# sa612_rcvr.net
KiCad netlist of a schematic drawn in EAGLE
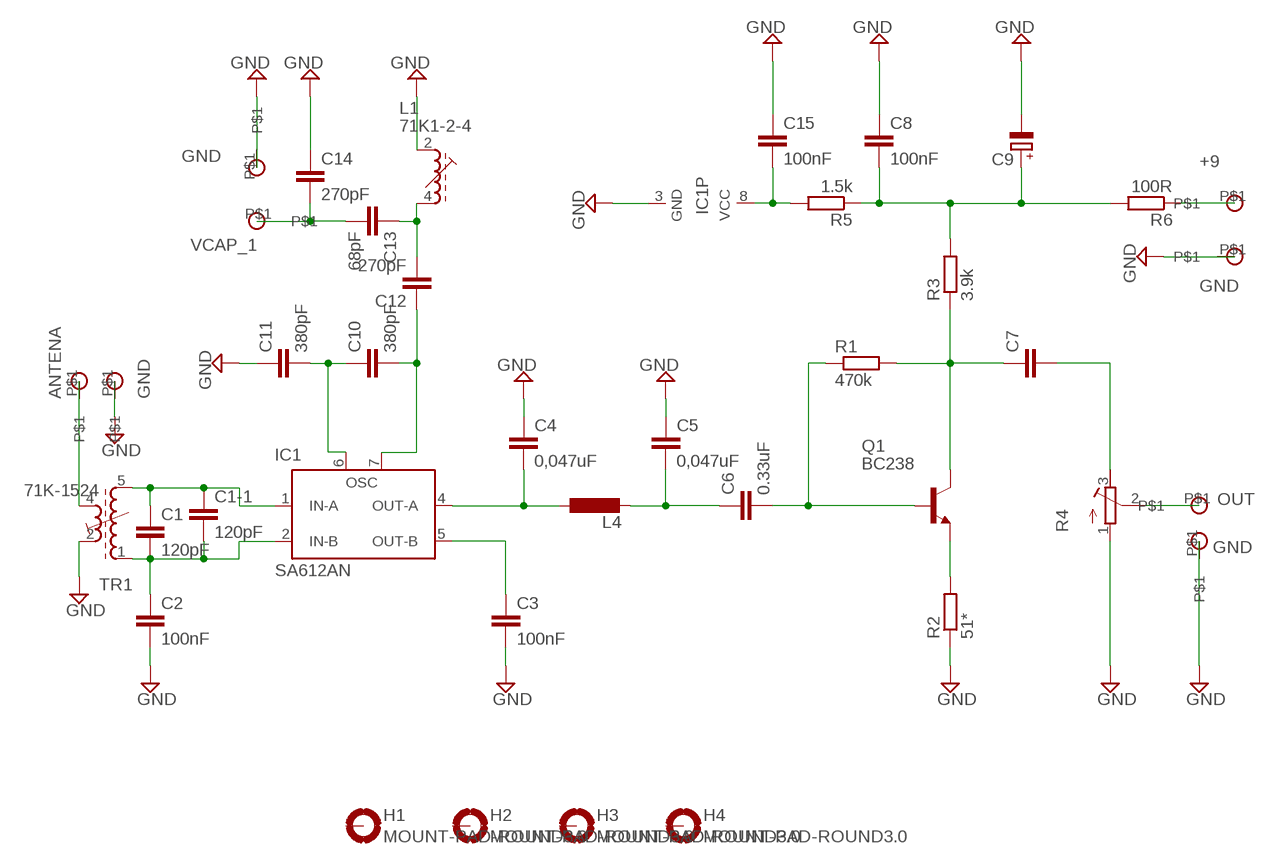
[diagram p0: schematic, sheet 1]

(export (version "E")
  (design (tool "Eeschema 10.0.6"))
  (components
    (comp (ref "C1")
      (value "120pF")
      (footprint "eagle-import:C0805K")
      (libsource (lib "eagle-import") (part "rcl_334_C-EUC0805K"))
    )
    (comp (ref "C1-1")
      (value "120pF")
      (footprint "eagle-import:C050-025X075")
      (libsource (lib "eagle-import") (part "C-EU050-025X075"))
    )
    (comp (ref "C2")
      (value "100nF")
      (footprint "eagle-import:C0805K")
      (libsource (lib "eagle-import") (part "rcl_334_C-EUC0805K"))
    )
    (comp (ref "C3")
      (value "100nF")
      (footprint "eagle-import:C0805K")
      (libsource (lib "eagle-import") (part "rcl_334_C-EUC0805K"))
    )
    (comp (ref "C4")
      (value "0,047uF")
      (footprint "eagle-import:C0805K")
      (libsource (lib "eagle-import") (part "rcl_334_C-EUC0805K"))
    )
    (comp (ref "C5")
      (value "0,047uF")
      (footprint "eagle-import:C0805K")
      (libsource (lib "eagle-import") (part "rcl_334_C-EUC0805K"))
    )
    (comp (ref "C6")
      (value "0.33uF")
      (footprint "eagle-import:C0805K")
      (libsource (lib "eagle-import") (part "rcl_334_C-EUC0805K"))
    )
    (comp (ref "C7")
      (value "C-EU050-025X075")
      (footprint "eagle-import:C050-025X075")
      (libsource (lib "eagle-import") (part "C-EU050-025X075"))
    )
    (comp (ref "C8")
      (value "100nF")
      (footprint "eagle-import:C0805K")
      (libsource (lib "eagle-import") (part "rcl_334_C-EUC0805K"))
    )
    (comp (ref "C9")
      (value "CPOL-EUE5-8.5")
      (footprint "eagle-import:E5-8,5")
      (libsource (lib "eagle-import") (part "CPOL-EUE5-8.5"))
    )
    (comp (ref "C10")
      (value "380pF")
      (footprint "eagle-import:C0805K")
      (libsource (lib "eagle-import") (part "rcl_334_C-EUC0805K"))
    )
    (comp (ref "C11")
      (value "380pF")
      (footprint "eagle-import:C0805K")
      (libsource (lib "eagle-import") (part "rcl_334_C-EUC0805K"))
    )
    (comp (ref "C12")
      (value "270pF")
      (footprint "eagle-import:C0805K")
      (libsource (lib "eagle-import") (part "rcl_334_C-EUC0805K"))
    )
    (comp (ref "C13")
      (value "68pF")
      (footprint "eagle-import:C0805K")
      (libsource (lib "eagle-import") (part "rcl_334_C-EUC0805K"))
    )
    (comp (ref "C14")
      (value "270pF")
      (footprint "eagle-import:C0805K")
      (libsource (lib "eagle-import") (part "rcl_334_C-EUC0805K"))
    )
    (comp (ref "C15")
      (value "100nF")
      (footprint "eagle-import:C0805K")
      (libsource (lib "eagle-import") (part "rcl_334_C-EUC0805K"))
    )
    (comp (ref "H1")
      (value "MOUNT-PAD-ROUND3.0")
      (footprint "eagle-import:3,0-PAD")
      (libsource (lib "eagle-import") (part "MOUNT-PAD-ROUND3.0"))
    )
    (comp (ref "H2")
      (value "MOUNT-PAD-ROUND3.0")
      (footprint "eagle-import:3,0-PAD")
      (libsource (lib "eagle-import") (part "MOUNT-PAD-ROUND3.0"))
    )
    (comp (ref "H3")
      (value "MOUNT-PAD-ROUND3.0")
      (footprint "eagle-import:3,0-PAD")
      (libsource (lib "eagle-import") (part "MOUNT-PAD-ROUND3.0"))
    )
    (comp (ref "H4")
      (value "MOUNT-PAD-ROUND3.0")
      (footprint "eagle-import:3,0-PAD")
      (libsource (lib "eagle-import") (part "MOUNT-PAD-ROUND3.0"))
    )
    (comp (ref "IC1")
      (value "SA612AN")
      (footprint "eagle-import:DIL08")
      (libsource (lib "eagle-import") (part "SA612AN"))
    )
    (comp (ref "L1")
      (value "71K1-2-4")
      (footprint "eagle-import:71K")
      (libsource (lib "eagle-import") (part "71K1-2-4"))
    )
    (comp (ref "L4")
      (value "L-EU6000-XXX-RC")
      (footprint "eagle-import:6000-XXXX-RC")
      (libsource (lib "eagle-import") (part "L-EU6000-XXX-RC"))
    )
    (comp (ref "Q1")
      (value "BC238")
      (footprint "eagle-import:TO92")
      (libsource (lib "eagle-import") (part "BC238"))
    )
    (comp (ref "R1")
      (value "470k")
      (footprint "eagle-import:R0805")
      (libsource (lib "eagle-import") (part "R-EU_R0805"))
    )
    (comp (ref "R2")
      (value "51*")
      (footprint "eagle-import:R0805")
      (libsource (lib "eagle-import") (part "R-EU_R0805"))
    )
    (comp (ref "R3")
      (value "3.9k")
      (footprint "eagle-import:R0805")
      (libsource (lib "eagle-import") (part "R-EU_R0805"))
    )
    (comp (ref "R4")
      (value "R-TRIMM64X")
      (footprint "eagle-import:RTRIM64X")
      (libsource (lib "eagle-import") (part "R-TRIMM64X"))
    )
    (comp (ref "R5")
      (value "1.5k")
      (footprint "eagle-import:R0805")
      (libsource (lib "eagle-import") (part "R-EU_R0805"))
    )
    (comp (ref "R6")
      (value "100R")
      (footprint "eagle-import:R0805")
      (libsource (lib "eagle-import") (part "R-EU_R0805"))
    )
    (comp (ref "TR1")
      (value "71K-1524")
      (footprint "eagle-import:71K")
      (libsource (lib "eagle-import") (part "71K-1524"))
    )
    (comp (ref "U$1")
      (value "SMD_PIN")
      (footprint "eagle-import:SMD_PIN")
      (libsource (lib "eagle-import") (part "SMD_PIN"))
    )
    (comp (ref "U$2")
      (value "SMD_PIN")
      (footprint "eagle-import:SMD_PIN")
      (libsource (lib "eagle-import") (part "SMD_PIN"))
    )
    (comp (ref "U$3")
      (value "SMD_PIN")
      (footprint "eagle-import:SMD_PIN")
      (libsource (lib "eagle-import") (part "SMD_PIN"))
    )
    (comp (ref "U$4")
      (value "SMD_PIN")
      (footprint "eagle-import:SMD_PIN")
      (libsource (lib "eagle-import") (part "SMD_PIN"))
    )
    (comp (ref "U$5")
      (value "SMD_PIN")
      (footprint "eagle-import:SMD_PIN")
      (libsource (lib "eagle-import") (part "SMD_PIN"))
    )
    (comp (ref "U$6")
      (value "SMD_PIN")
      (footprint "eagle-import:SMD_PIN")
      (libsource (lib "eagle-import") (part "SMD_PIN"))
    )
    (comp (ref "U$7")
      (value "SMD_PIN")
      (footprint "eagle-import:SMD_PIN")
      (libsource (lib "eagle-import") (part "SMD_PIN"))
    )
    (comp (ref "U$8")
      (value "SMD_PIN")
      (footprint "eagle-import:SMD_PIN")
      (libsource (lib "eagle-import") (part "SMD_PIN"))
    )
  )
  (nets
    (net (code "1") (name "/+9") (class "Default")
      (node (ref "R6") (pin "1") (pinfunction "1_1") (pintype "passive"))
      (node (ref "U$5") (pin "P$1") (pinfunction "P$1_P$1") (pintype "bidirectional"))
    )
    (net (code "2") (name "/ANTENA") (class "Default")
      (node (ref "TR1") (pin "4") (pinfunction "E2_4") (pintype "passive"))
      (node (ref "U$3") (pin "P$1") (pinfunction "P$1_P$1") (pintype "bidirectional"))
    )
    (net (code "3") (name "/OUT") (class "Default")
      (node (ref "R4") (pin "2") (pinfunction "S_2") (pintype "passive"))
      (node (ref "U$1") (pin "P$1") (pinfunction "P$1_P$1") (pintype "bidirectional"))
    )
    (net (code "4") (name "/VCAP_1") (class "Default")
      (node (ref "C13") (pin "2") (pinfunction "2_2") (pintype "passive"))
      (node (ref "C14") (pin "2") (pinfunction "2_2") (pintype "passive"))
      (node (ref "U$7") (pin "P$1") (pinfunction "P$1_P$1") (pintype "bidirectional"))
    )
    (net (code "5") (name "GND") (class "Default")
      (node (ref "C11") (pin "1") (pinfunction "1_1") (pintype "passive"))
      (node (ref "C14") (pin "1") (pinfunction "1_1") (pintype "passive"))
      (node (ref "C15") (pin "1") (pinfunction "1_1") (pintype "passive"))
      (node (ref "C2") (pin "2") (pinfunction "2_2") (pintype "passive"))
      (node (ref "C3") (pin "2") (pinfunction "2_2") (pintype "passive"))
      (node (ref "C4") (pin "1") (pinfunction "1_1") (pintype "passive"))
      (node (ref "C5") (pin "1") (pinfunction "1_1") (pintype "passive"))
      (node (ref "C8") (pin "1") (pinfunction "1_1") (pintype "passive"))
      (node (ref "C9") (pin "-") (pinfunction "-_-") (pintype "passive"))
      (node (ref "IC1") (pin "3") (pinfunction "GND_3") (pintype "power_in"))
      (node (ref "L1") (pin "2") (pinfunction "A_2") (pintype "passive"))
      (node (ref "R2") (pin "1") (pinfunction "1_1") (pintype "passive"))
      (node (ref "R4") (pin "1") (pinfunction "A_1") (pintype "passive"))
      (node (ref "TR1") (pin "2") (pinfunction "A2_2") (pintype "passive"))
      (node (ref "U$2") (pin "P$1") (pinfunction "P$1_P$1") (pintype "bidirectional"))
      (node (ref "U$4") (pin "P$1") (pinfunction "P$1_P$1") (pintype "bidirectional"))
      (node (ref "U$6") (pin "P$1") (pinfunction "P$1_P$1") (pintype "bidirectional"))
      (node (ref "U$8") (pin "P$1") (pinfunction "P$1_P$1") (pintype "bidirectional"))
    )
    (net (code "6") (name "Net-(C5-Pad2)") (class "Default")
      (node (ref "C5") (pin "2") (pinfunction "2_2") (pintype "passive"))
      (node (ref "C6") (pin "1") (pinfunction "1_1") (pintype "passive"))
      (node (ref "L4") (pin "2") (pinfunction "2_2") (pintype "passive"))
    )
    (net (code "7") (name "Net-(C8-Pad2)") (class "Default")
      (node (ref "C8") (pin "2") (pinfunction "2_2") (pintype "passive"))
      (node (ref "C9") (pin "+") (pinfunction "+_+") (pintype "passive"))
      (node (ref "R3") (pin "2") (pinfunction "2_2") (pintype "passive"))
      (node (ref "R5") (pin "1") (pinfunction "1_1") (pintype "passive"))
      (node (ref "R6") (pin "2") (pinfunction "2_2") (pintype "passive"))
    )
    (net (code "8") (name "Net-(IC1A-IN-A)") (class "Default")
      (node (ref "C1") (pin "1") (pinfunction "1_1") (pintype "passive"))
      (node (ref "C1-1") (pin "1") (pinfunction "1_1") (pintype "passive"))
      (node (ref "IC1") (pin "1") (pinfunction "IN-A_1") (pintype "input"))
      (node (ref "TR1") (pin "5") (pinfunction "E1_5") (pintype "passive"))
    )
    (net (code "9") (name "Net-(IC1A-IN-B)") (class "Default")
      (node (ref "C1") (pin "2") (pinfunction "2_2") (pintype "passive"))
      (node (ref "C1-1") (pin "2") (pinfunction "2_2") (pintype "passive"))
      (node (ref "C2") (pin "1") (pinfunction "1_1") (pintype "passive"))
      (node (ref "IC1") (pin "2") (pinfunction "IN-B_2") (pintype "input"))
      (node (ref "TR1") (pin "1") (pinfunction "A1_1") (pintype "passive"))
    )
    (net (code "10") (name "Net-(IC1A-OSC')") (class "Default")
      (node (ref "C10") (pin "2") (pinfunction "2_2") (pintype "passive"))
      (node (ref "C12") (pin "1") (pinfunction "1_1") (pintype "passive"))
      (node (ref "IC1") (pin "7") (pinfunction "OSC'_7") (pintype "passive"))
    )
    (net (code "11") (name "Net-(IC1A-OSC)") (class "Default")
      (node (ref "C10") (pin "1") (pinfunction "1_1") (pintype "passive"))
      (node (ref "C11") (pin "2") (pinfunction "2_2") (pintype "passive"))
      (node (ref "IC1") (pin "6") (pinfunction "OSC_6") (pintype "passive"))
    )
    (net (code "12") (name "Net-(IC1A-OUT-A)") (class "Default")
      (node (ref "C4") (pin "2") (pinfunction "2_2") (pintype "passive"))
      (node (ref "IC1") (pin "4") (pinfunction "OUT-A_4") (pintype "input"))
      (node (ref "L4") (pin "1") (pinfunction "1_1") (pintype "passive"))
    )
    (net (code "13") (name "Net-(IC1A-OUT-B)") (class "Default")
      (node (ref "C3") (pin "1") (pinfunction "1_1") (pintype "passive"))
      (node (ref "IC1") (pin "5") (pinfunction "OUT-B_5") (pintype "input"))
    )
    (net (code "14") (name "Net-(IC1B-VCC)") (class "Default")
      (node (ref "C15") (pin "2") (pinfunction "2_2") (pintype "passive"))
      (node (ref "IC1") (pin "8") (pinfunction "VCC_8") (pintype "power_in"))
      (node (ref "R5") (pin "2") (pinfunction "2_2") (pintype "passive"))
    )
    (net (code "15") (name "Net-(L1A-E)") (class "Default")
      (node (ref "C12") (pin "2") (pinfunction "2_2") (pintype "passive"))
      (node (ref "C13") (pin "1") (pinfunction "1_1") (pintype "passive"))
      (node (ref "L1") (pin "4") (pinfunction "E_4") (pintype "passive"))
    )
    (net (code "16") (name "Net-(Q1-B)") (class "Default")
      (node (ref "C6") (pin "2") (pinfunction "2_2") (pintype "passive"))
      (node (ref "Q1") (pin "2") (pinfunction "B_2") (pintype "passive"))
      (node (ref "R1") (pin "1") (pinfunction "1_1") (pintype "passive"))
    )
    (net (code "17") (name "Net-(Q1-C)") (class "Default")
      (node (ref "C7") (pin "1") (pinfunction "1_1") (pintype "passive"))
      (node (ref "Q1") (pin "3") (pinfunction "C_3") (pintype "passive"))
      (node (ref "R1") (pin "2") (pinfunction "2_2") (pintype "passive"))
      (node (ref "R3") (pin "1") (pinfunction "1_1") (pintype "passive"))
    )
    (net (code "18") (name "Net-(Q1-E)") (class "Default")
      (node (ref "Q1") (pin "1") (pinfunction "E_1") (pintype "passive"))
      (node (ref "R2") (pin "2") (pinfunction "2_2") (pintype "passive"))
    )
    (net (code "19") (name "Net-(R4-E)") (class "Default")
      (node (ref "C7") (pin "2") (pinfunction "2_2") (pintype "passive"))
      (node (ref "R4") (pin "3") (pinfunction "E_3") (pintype "passive"))
    )
    (net (code "20") (name "unconnected-(H1-MOUNT-PadB3,0)") (class "Default")
      (node (ref "H1") (pin "B3,0") (pinfunction "MOUNT_B3,0") (pintype "passive"))
    )
    (net (code "21") (name "unconnected-(H2-MOUNT-PadB3,0)") (class "Default")
      (node (ref "H2") (pin "B3,0") (pinfunction "MOUNT_B3,0") (pintype "passive"))
    )
    (net (code "22") (name "unconnected-(H3-MOUNT-PadB3,0)") (class "Default")
      (node (ref "H3") (pin "B3,0") (pinfunction "MOUNT_B3,0") (pintype "passive"))
    )
    (net (code "23") (name "unconnected-(H4-MOUNT-PadB3,0)") (class "Default")
      (node (ref "H4") (pin "B3,0") (pinfunction "MOUNT_B3,0") (pintype "passive"))
    )
  )
)
